# Motores.net
KiCad netlist of a schematic drawn in EAGLE
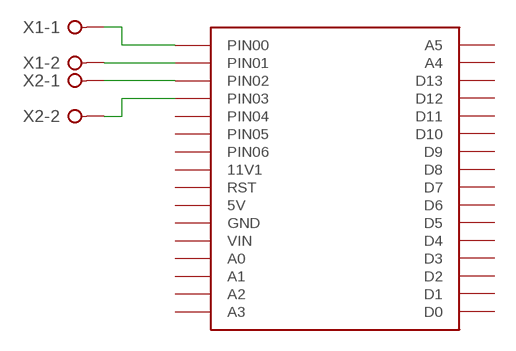
[diagram p0: schematic, sheet 1]

(export (version "E")
  (design (tool "Eeschema 10.0.6"))
  (components
    (comp (ref "U$1")
      (value "BASE-FINAL")
      (footprint "eagle-import:BASE-FINAL")
      (libsource (lib "eagle-import") (part "BASE-FINAL"))
    )
    (comp (ref "X1")
      (value "W237-02P")
      (footprint "eagle-import:W237-132")
      (libsource (lib "eagle-import") (part "W237-02P"))
    )
    (comp (ref "X2")
      (value "W237-02P")
      (footprint "eagle-import:W237-132")
      (libsource (lib "eagle-import") (part "W237-02P"))
    )
  )
  (nets
    (net (code "1") (name "Net-(X1A-KL)") (class "Default")
      (node (ref "U$1") (pin "PIN00") (pinfunction "PIN00_PIN00") (pintype "bidirectional"))
      (node (ref "X1") (pin "1") (pinfunction "KL_1") (pintype "passive"))
    )
    (net (code "2") (name "Net-(X1B-KL)") (class "Default")
      (node (ref "U$1") (pin "PIN01") (pinfunction "PIN01_PIN01") (pintype "bidirectional"))
      (node (ref "X1") (pin "2") (pinfunction "KL_2") (pintype "passive"))
    )
    (net (code "3") (name "Net-(X2A-KL)") (class "Default")
      (node (ref "U$1") (pin "PIN02") (pinfunction "PIN02_PIN02") (pintype "bidirectional"))
      (node (ref "X2") (pin "1") (pinfunction "KL_1") (pintype "passive"))
    )
    (net (code "4") (name "Net-(X2B-KL)") (class "Default")
      (node (ref "U$1") (pin "PIN03") (pinfunction "PIN03_PIN03") (pintype "bidirectional"))
      (node (ref "X2") (pin "2") (pinfunction "KL_2") (pintype "passive"))
    )
    (net (code "5") (name "unconnected-(U$1-11V1-Pad12V)") (class "Default")
      (node (ref "U$1") (pin "12V") (pinfunction "11V1_12V") (pintype "bidirectional"))
    )
    (net (code "6") (name "unconnected-(U$1-D0-Pad0)") (class "Default")
      (node (ref "U$1") (pin "0") (pinfunction "D0_0") (pintype "bidirectional"))
    )
    (net (code "7") (name "unconnected-(U$1-D1-Pad1)") (class "Default")
      (node (ref "U$1") (pin "1") (pinfunction "D1_1") (pintype "bidirectional"))
    )
    (net (code "8") (name "unconnected-(U$1-D2-Pad2)") (class "Default")
      (node (ref "U$1") (pin "2") (pinfunction "D2_2") (pintype "bidirectional"))
    )
    (net (code "9") (name "unconnected-(U$1-D3-Pad3)") (class "Default")
      (node (ref "U$1") (pin "3") (pinfunction "D3_3") (pintype "bidirectional"))
    )
    (net (code "10") (name "unconnected-(U$1-D4-Pad4)") (class "Default")
      (node (ref "U$1") (pin "4") (pinfunction "D4_4") (pintype "bidirectional"))
    )
    (net (code "11") (name "unconnected-(U$1-D5-Pad5)") (class "Default")
      (node (ref "U$1") (pin "5") (pinfunction "D5_5") (pintype "bidirectional"))
    )
    (net (code "12") (name "unconnected-(U$1-D6-Pad6)") (class "Default")
      (node (ref "U$1") (pin "6") (pinfunction "D6_6") (pintype "bidirectional"))
    )
    (net (code "13") (name "unconnected-(U$1-D7-Pad7)") (class "Default")
      (node (ref "U$1") (pin "7") (pinfunction "D7_7") (pintype "bidirectional"))
    )
    (net (code "14") (name "unconnected-(U$1-D8-Pad8)") (class "Default")
      (node (ref "U$1") (pin "8") (pinfunction "D8_8") (pintype "bidirectional"))
    )
    (net (code "15") (name "unconnected-(U$1-D9-Pad9)") (class "Default")
      (node (ref "U$1") (pin "9") (pinfunction "D9_9") (pintype "bidirectional"))
    )
    (net (code "16") (name "unconnected-(U$1-D10-Pad10)") (class "Default")
      (node (ref "U$1") (pin "10") (pinfunction "D10_10") (pintype "bidirectional"))
    )
    (net (code "17") (name "unconnected-(U$1-D11-Pad11)") (class "Default")
      (node (ref "U$1") (pin "11") (pinfunction "D11_11") (pintype "bidirectional"))
    )
    (net (code "18") (name "unconnected-(U$1-D12-Pad12)") (class "Default")
      (node (ref "U$1") (pin "12") (pinfunction "D12_12") (pintype "bidirectional"))
    )
    (net (code "19") (name "unconnected-(U$1-D13-Pad13)") (class "Default")
      (node (ref "U$1") (pin "13") (pinfunction "D13_13") (pintype "bidirectional"))
    )
    (net (code "20") (name "unconnected-(U$1-Pad5V)") (class "Default")
      (node (ref "U$1") (pin "5V") (pinfunction "5V_5V") (pintype "bidirectional"))
    )
    (net (code "21") (name "unconnected-(U$1-PadA0)") (class "Default")
      (node (ref "U$1") (pin "A0") (pinfunction "A0_A0") (pintype "bidirectional"))
    )
    (net (code "22") (name "unconnected-(U$1-PadA1)") (class "Default")
      (node (ref "U$1") (pin "A1") (pinfunction "A1_A1") (pintype "bidirectional"))
    )
    (net (code "23") (name "unconnected-(U$1-PadA2)") (class "Default")
      (node (ref "U$1") (pin "A2") (pinfunction "A2_A2") (pintype "bidirectional"))
    )
    (net (code "24") (name "unconnected-(U$1-PadA3)") (class "Default")
      (node (ref "U$1") (pin "A3") (pinfunction "A3_A3") (pintype "bidirectional"))
    )
    (net (code "25") (name "unconnected-(U$1-PadA4)") (class "Default")
      (node (ref "U$1") (pin "A4") (pinfunction "A4_A4") (pintype "bidirectional"))
    )
    (net (code "26") (name "unconnected-(U$1-PadA5)") (class "Default")
      (node (ref "U$1") (pin "A5") (pinfunction "A5_A5") (pintype "bidirectional"))
    )
    (net (code "27") (name "unconnected-(U$1-PadGND)") (class "Default")
      (node (ref "U$1") (pin "GND") (pinfunction "GND_GND") (pintype "bidirectional"))
    )
    (net (code "28") (name "unconnected-(U$1-PadPIN04)") (class "Default")
      (node (ref "U$1") (pin "PIN04") (pinfunction "PIN04_PIN04") (pintype "bidirectional"))
    )
    (net (code "29") (name "unconnected-(U$1-PadPIN05)") (class "Default")
      (node (ref "U$1") (pin "PIN05") (pinfunction "PIN05_PIN05") (pintype "bidirectional"))
    )
    (net (code "30") (name "unconnected-(U$1-PadPIN06)") (class "Default")
      (node (ref "U$1") (pin "PIN06") (pinfunction "PIN06_PIN06") (pintype "bidirectional"))
    )
    (net (code "31") (name "unconnected-(U$1-PadRST)") (class "Default")
      (node (ref "U$1") (pin "RST") (pinfunction "RST_RST") (pintype "bidirectional"))
    )
    (net (code "32") (name "unconnected-(U$1-PadVIN)") (class "Default")
      (node (ref "U$1") (pin "VIN") (pinfunction "VIN_VIN") (pintype "bidirectional"))
    )
  )
)
